# ch4.net
KiCad netlist of a schematic drawn in EAGLE
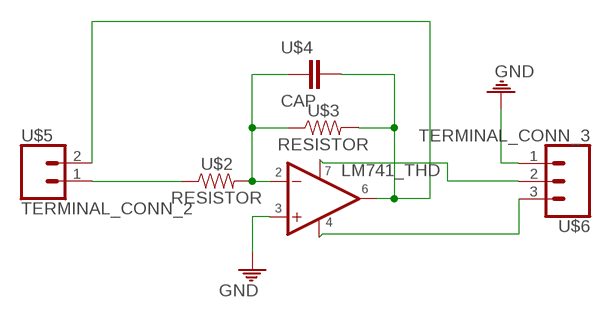
[diagram p0: schematic, sheet 1]

(export (version "E")
  (design (tool "Eeschema 10.0.6"))
  (components
    (comp (ref "U$1")
      (value "IC-LM741")
      (footprint "eagle-import:IC-LM741")
      (libsource (lib "eagle-import") (part "IC-LM741"))
    )
    (comp (ref "U$2")
      (value "RESISTOR")
      (footprint "eagle-import:RESISTOR")
      (libsource (lib "eagle-import") (part "RESISTOR"))
    )
    (comp (ref "U$3")
      (value "RESISTOR")
      (footprint "eagle-import:RESISTOR")
      (libsource (lib "eagle-import") (part "RESISTOR"))
    )
    (comp (ref "U$4")
      (value "CAP")
      (footprint "eagle-import:CAP-TH")
      (libsource (lib "eagle-import") (part "CAP"))
    )
    (comp (ref "U$5")
      (value "TERMINAL_CONN_2")
      (footprint "eagle-import:TERMINAL_CONN_2")
      (libsource (lib "eagle-import") (part "TERMINAL_CONN_2"))
    )
    (comp (ref "U$6")
      (value "TERMINAL_CONN_3")
      (footprint "eagle-import:TERMINAL-CONN_3")
      (libsource (lib "eagle-import") (part "TERMINAL_CONN_3"))
    )
  )
  (nets
    (net (code "1") (name "GND") (class "Default")
      (node (ref "U$1") (pin "3") (pinfunction "+IN_3") (pintype "input"))
      (node (ref "U$6") (pin "1") (pinfunction "1_1") (pintype "passive"))
    )
    (net (code "2") (name "Net-(U$1--IN)") (class "Default")
      (node (ref "U$1") (pin "2") (pinfunction "-IN_2") (pintype "input"))
      (node (ref "U$2") (pin "2") (pinfunction "2_2") (pintype "passive"))
      (node (ref "U$3") (pin "1") (pinfunction "1_1") (pintype "passive"))
      (node (ref "U$4") (pin "1") (pinfunction "1_1") (pintype "passive"))
    )
    (net (code "3") (name "Net-(U$1-OUT)") (class "Default")
      (node (ref "U$1") (pin "6") (pinfunction "OUT_6") (pintype "output"))
      (node (ref "U$3") (pin "2") (pinfunction "2_2") (pintype "passive"))
      (node (ref "U$4") (pin "2") (pinfunction "2_2") (pintype "passive"))
      (node (ref "U$5") (pin "2") (pinfunction "2_2") (pintype "passive"))
    )
    (net (code "4") (name "Net-(U$1-Pad4)") (class "Default")
      (node (ref "U$1") (pin "4") (pinfunction "4_4") (pintype "bidirectional"))
      (node (ref "U$6") (pin "3") (pinfunction "3_3") (pintype "passive"))
    )
    (net (code "5") (name "Net-(U$1-Pad7)") (class "Default")
      (node (ref "U$1") (pin "7") (pinfunction "7_7") (pintype "bidirectional"))
      (node (ref "U$6") (pin "2") (pinfunction "2_2") (pintype "passive"))
    )
    (net (code "6") (name "Net-(U$2-Pad1)") (class "Default")
      (node (ref "U$2") (pin "1") (pinfunction "1_1") (pintype "passive"))
      (node (ref "U$5") (pin "1") (pinfunction "1_1") (pintype "passive"))
    )
  )
)
